# lab2_zhernakov_buck.net
KiCad netlist of a schematic drawn in Altium Designer
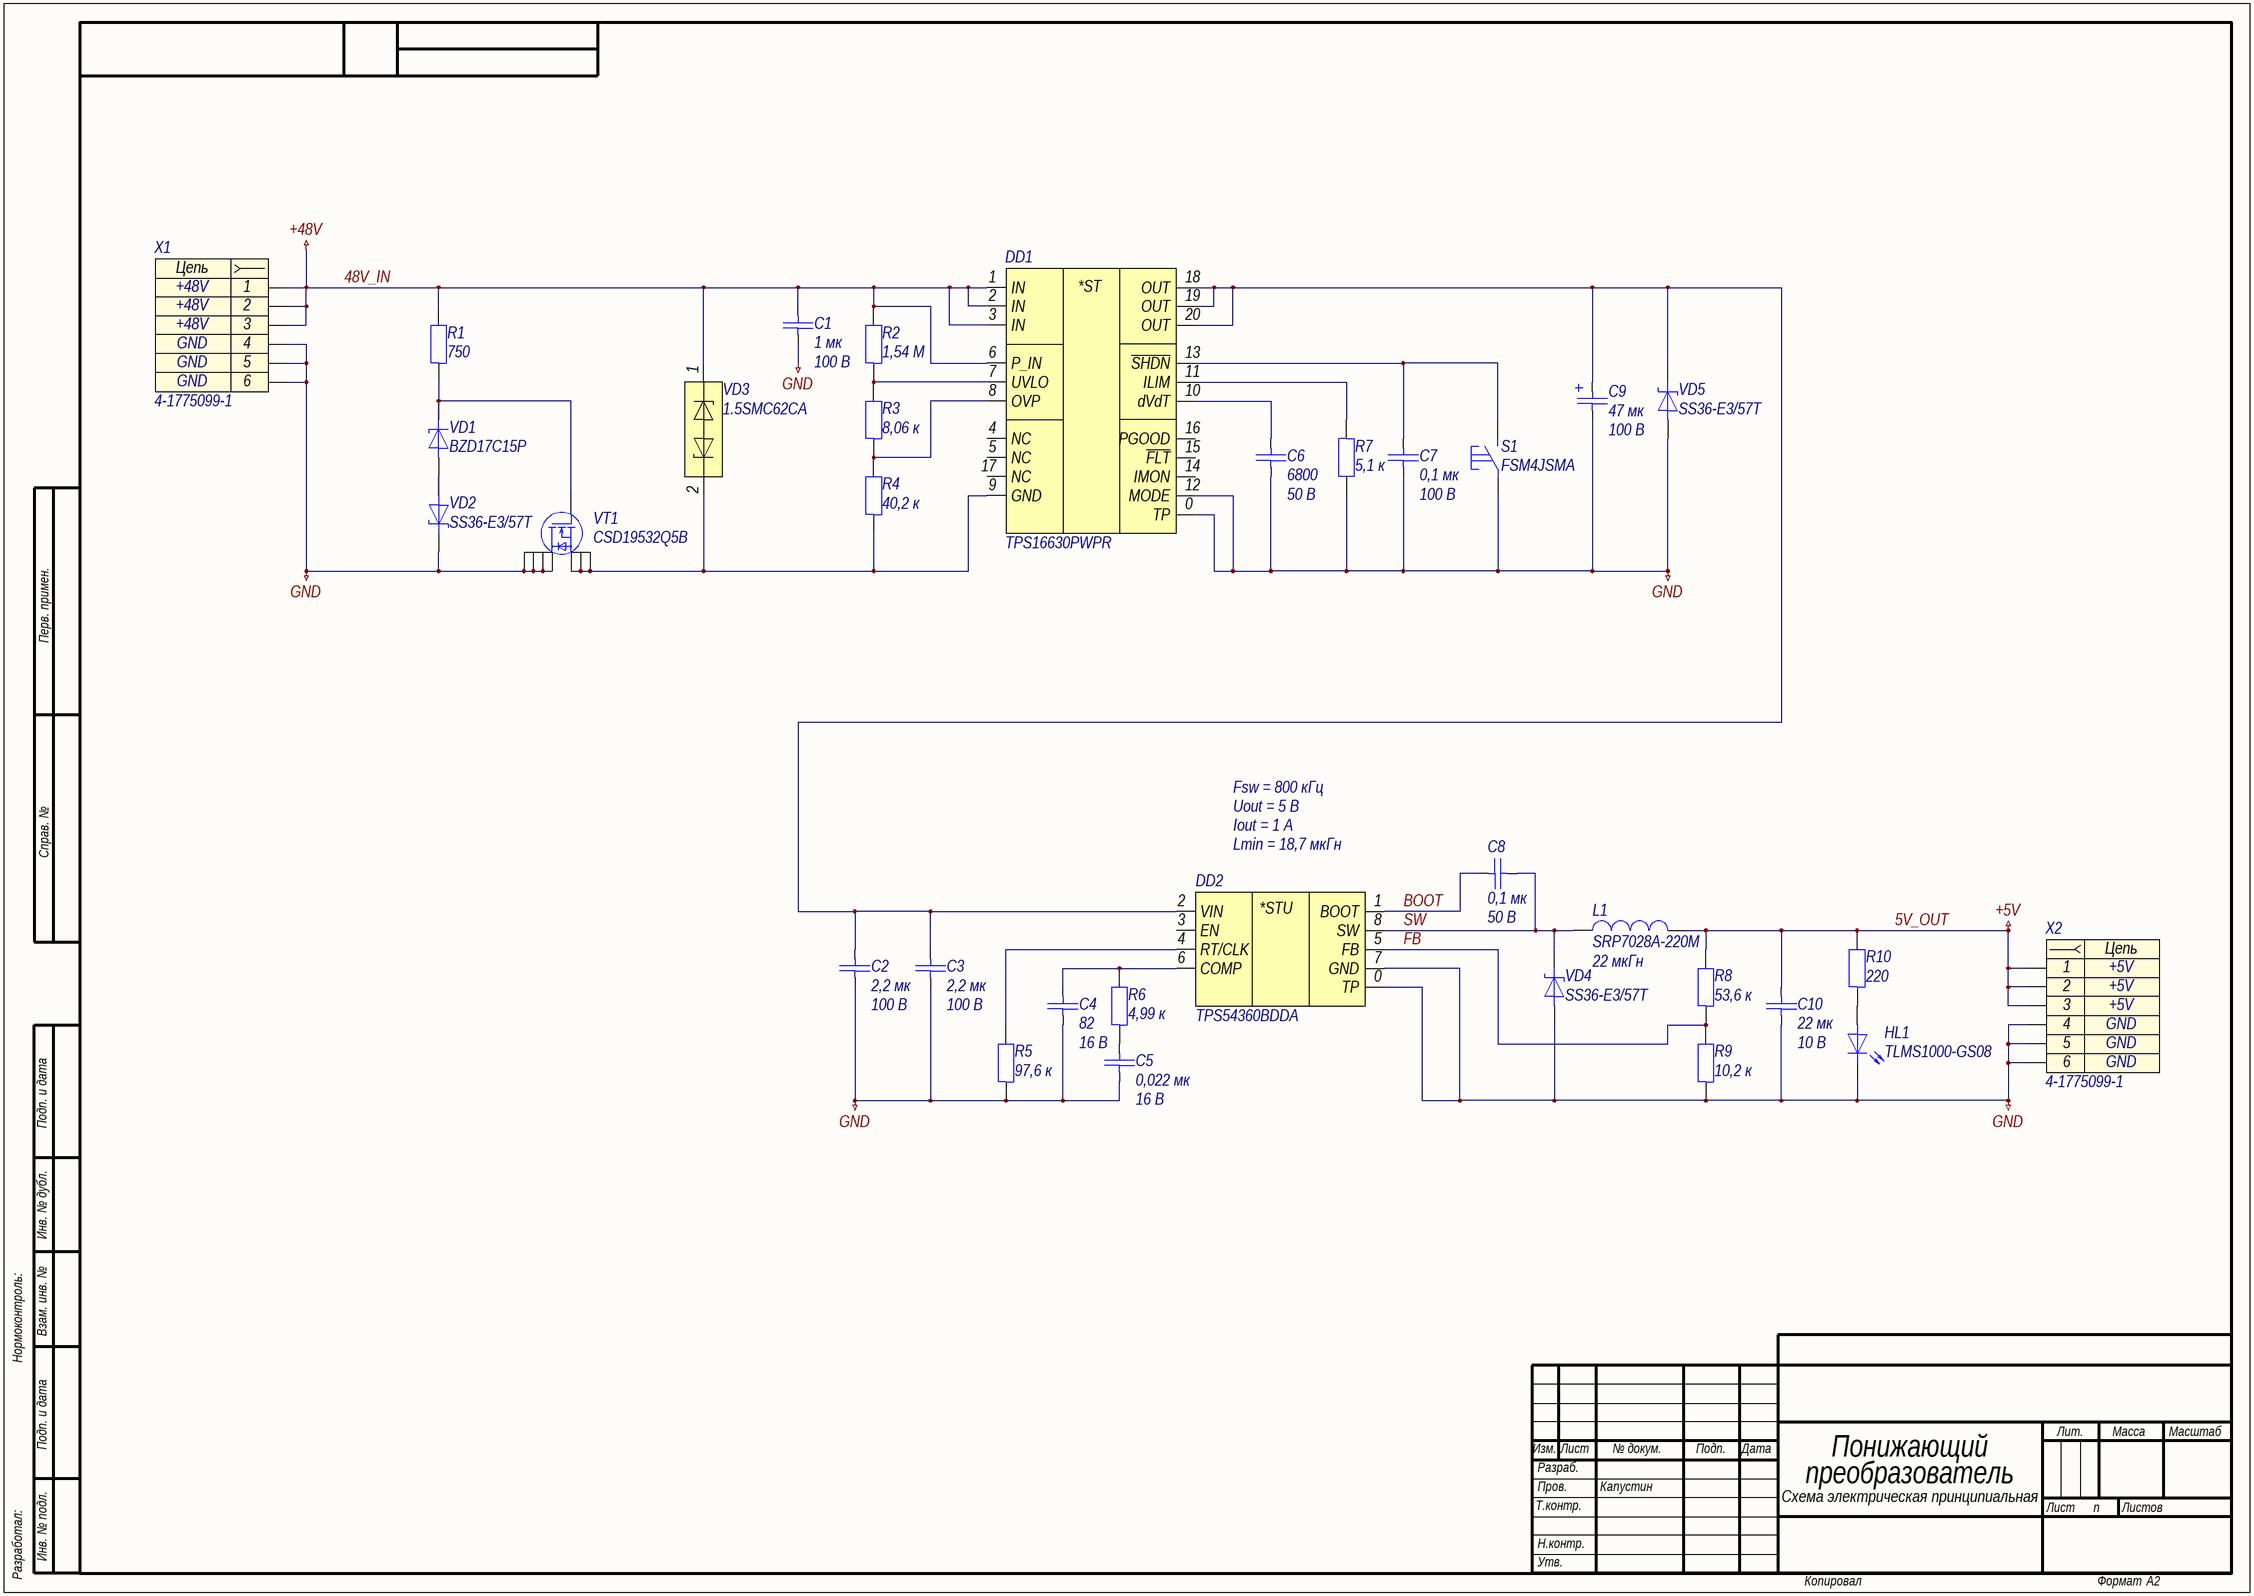
[diagram p0: lab2_zhernakov_buck.SchDoc]

(export (version "E")
  (design (tool "Eeschema 10.0.6"))
  (components
    (comp (ref "C1")
      (value "1 мк")
      (footprint "C1206")
      (description "=Описание")
      (fields (field (name "НАПРЯЖЕНИЕ") "100 В"))
      (libsource (lib "Database_Students") (part "C-NONPOLAR"))
    )
    (comp (ref "C2")
      (value "2,2 мк")
      (footprint "C1206")
      (description "=Описание")
      (fields (field (name "НАПРЯЖЕНИЕ") "100 В"))
      (libsource (lib "Database_Students") (part "C-NONPOLAR"))
    )
    (comp (ref "C3")
      (value "2,2 мк")
      (footprint "C1206")
      (description "=Описание")
      (fields (field (name "НАПРЯЖЕНИЕ") "100 В"))
      (libsource (lib "Database_Students") (part "C-NONPOLAR"))
    )
    (comp (ref "C4")
      (value "82")
      (footprint "C0603")
      (description "=Описание")
      (fields (field (name "НАПРЯЖЕНИЕ") "16 В"))
      (libsource (lib "Database_Students") (part "C-NONPOLAR"))
    )
    (comp (ref "C5")
      (value "0,022 мк")
      (footprint "C0201")
      (description "=Описание")
      (fields (field (name "НАПРЯЖЕНИЕ") "16 В"))
      (libsource (lib "Database_Students") (part "C-NONPOLAR"))
    )
    (comp (ref "C6")
      (value "6800")
      (footprint "C0402")
      (description "=Описание")
      (fields (field (name "НАПРЯЖЕНИЕ") "50 В"))
      (libsource (lib "Database_Students") (part "C-NONPOLAR"))
    )
    (comp (ref "C7")
      (value "0,1 мк")
      (footprint "C0603")
      (description "=Описание")
      (fields (field (name "НАПРЯЖЕНИЕ") "100 В"))
      (libsource (lib "Database_Students") (part "C-NONPOLAR"))
    )
    (comp (ref "C8")
      (value "0,1 мк")
      (footprint "C0603")
      (description "=Описание")
      (fields (field (name "НАПРЯЖЕНИЕ") "50 В"))
      (libsource (lib "Database_Students") (part "C-NONPOLAR"))
    )
    (comp (ref "C9")
      (value "47 мк")
      (footprint "CAPAE-1000X1000X1200")
      (description "=Описание")
      (fields (field (name "НАПРЯЖЕНИЕ") "100 В"))
      (libsource (lib "Database_Students") (part "C-POLAR"))
    )
    (comp (ref "C10")
      (value "22 мк")
      (footprint "C0603")
      (description "=Описание")
      (fields (field (name "НАПРЯЖЕНИЕ") "10 В"))
      (libsource (lib "Database_Students") (part "C-NONPOLAR"))
    )
    (comp (ref "DD1")
      (value "TPS16630PWPR")
      (footprint "HTSSOP-20")
      (description "=Описание")
      (libsource (lib "Database_Students") (part "TPS16630PWPR"))
    )
    (comp (ref "DD2")
      (value "TPS54360BDDA")
      (footprint "HSOIC-8")
      (description "=Описание")
      (libsource (lib "Database_Students") (part "TPS54360BDDA"))
    )
    (comp (ref "HL1")
      (value "TLMS1000-GS08")
      (footprint "HL0603")
      (description "=Описание")
      (libsource (lib "Database_Students") (part "HL-COMMON"))
    )
    (comp (ref "L1")
      (value "SRP7028A-220M")
      (footprint "SRP-2-670X660X280")
      (description "=Описание")
      (fields (field (name "ИНДУКТИВНОСТЬ") "22 мкГн"))
      (libsource (lib "Database_Students") (part "INDUCTOR-COMMON"))
    )
    (comp (ref "R1")
      (value "750")
      (footprint "R0603")
      (description "=Описание")
      (libsource (lib "Database_Students") (part "R-COMMON"))
    )
    (comp (ref "R2")
      (value "1,54 М")
      (footprint "R0603")
      (description "=Описание")
      (libsource (lib "Database_Students") (part "R-COMMON"))
    )
    (comp (ref "R3")
      (value "8,06 к")
      (footprint "R0603")
      (description "=Описание")
      (libsource (lib "Database_Students") (part "R-COMMON"))
    )
    (comp (ref "R4")
      (value "40,2 к")
      (footprint "R0603")
      (description "=Описание")
      (libsource (lib "Database_Students") (part "R-COMMON"))
    )
    (comp (ref "R5")
      (value "97,6 к")
      (footprint "R0603")
      (description "=Описание")
      (libsource (lib "Database_Students") (part "R-COMMON"))
    )
    (comp (ref "R6")
      (value "4,99 к")
      (footprint "R0603")
      (description "=Описание")
      (libsource (lib "Database_Students") (part "R-COMMON"))
    )
    (comp (ref "R7")
      (value "5,1 к")
      (footprint "R0603")
      (description "=Описание")
      (libsource (lib "Database_Students") (part "R-COMMON"))
    )
    (comp (ref "R8")
      (value "53,6 к")
      (footprint "R0603")
      (description "=Описание")
      (libsource (lib "Database_Students") (part "R-COMMON"))
    )
    (comp (ref "R9")
      (value "10,2 к")
      (footprint "R0603")
      (description "=Описание")
      (libsource (lib "Database_Students") (part "R-COMMON"))
    )
    (comp (ref "R10")
      (value "220")
      (footprint "R0603")
      (description "=Описание")
      (libsource (lib "Database_Students") (part "R-COMMON"))
    )
    (comp (ref "S1")
      (value "FSM4JSMA")
      (footprint "FSM4JSMA")
      (description "=Описание")
      (libsource (lib "Database_Students") (part "BUTTON"))
    )
    (comp (ref "VD1")
      (value "BZD17C15P")
      (footprint "DO-219AB")
      (description "=Описание")
      (libsource (lib "Database_Students") (part "ZENER-DIODE"))
    )
    (comp (ref "VD2")
      (value "SS36-E3/57T")
      (footprint "DO-214AB")
      (description "=Описание")
      (libsource (lib "Database_Students") (part "DIODE-SCHOTTKY"))
    )
    (comp (ref "VD3")
      (value "1.5SMC62CA")
      (footprint "DO-214AB")
      (description "=Описание")
      (libsource (lib "Database_Students") (part "ZENER-BI-DIRECTIONAL"))
    )
    (comp (ref "VD4")
      (value "SS36-E3/57T")
      (footprint "DO-214AB")
      (description "=Описание")
      (libsource (lib "Database_Students") (part "DIODE-SCHOTTKY"))
    )
    (comp (ref "VD5")
      (value "SS36-E3/57T")
      (footprint "DO-214AB")
      (description "=Описание")
      (libsource (lib "Database_Students") (part "DIODE-SCHOTTKY"))
    )
    (comp (ref "VT1")
      (value "CSD19532Q5B")
      (footprint "SON-8")
      (description "=Описание")
      (libsource (lib "Database_Students") (part "TRANSISTOR_7_N"))
    )
    (comp (ref "X1")
      (value "4-1775099-1")
      (footprint "4-1775099-1")
      (description "=Описание")
      (libsource (lib "Database_Students") (part "HEADER-6-SCT"))
    )
    (comp (ref "X2")
      (value "4-1775099-1")
      (footprint "4-1775099-1")
      (description "=Описание")
      (libsource (lib "") (part "HEADER-6-SCT_1"))
    )
  )
  (nets
    (net (code "1") (name "+5V") (class "Default")
      (node (ref "C10") (pin "1") (pinfunction "1_1") (pintype "passive"))
      (node (ref "L1") (pin "2") (pinfunction "2_2") (pintype "passive"))
      (node (ref "R10") (pin "2") (pinfunction "2_2") (pintype "passive"))
      (node (ref "R8") (pin "2") (pinfunction "2_2") (pintype "passive"))
      (node (ref "X2") (pin "1") (pinfunction "1_1") (pintype "passive"))
      (node (ref "X2") (pin "2") (pinfunction "2_2") (pintype "passive"))
      (node (ref "X2") (pin "3") (pinfunction "3_3") (pintype "passive"))
    )
    (net (code "2") (name "+48V") (class "Default")
      (node (ref "C1") (pin "1") (pinfunction "1_1") (pintype "passive"))
      (node (ref "DD1") (pin "1") (pinfunction "IN_1") (pintype "passive"))
      (node (ref "DD1") (pin "2") (pinfunction "IN_2") (pintype "passive"))
      (node (ref "DD1") (pin "3") (pinfunction "IN_3") (pintype "passive"))
      (node (ref "DD1") (pin "6") (pinfunction "P_IN_6") (pintype "passive"))
      (node (ref "R1") (pin "2") (pinfunction "2_2") (pintype "passive"))
      (node (ref "R2") (pin "2") (pinfunction "2_2") (pintype "passive"))
      (node (ref "VD3") (pin "1") (pinfunction "1_1") (pintype "passive"))
      (node (ref "X1") (pin "1") (pinfunction "1_1") (pintype "passive"))
      (node (ref "X1") (pin "2") (pinfunction "2_2") (pintype "passive"))
      (node (ref "X1") (pin "3") (pinfunction "3_3") (pintype "passive"))
    )
    (net (code "3") (name "/BOOT") (class "Default")
      (node (ref "C8") (pin "2") (pinfunction "2_2") (pintype "passive"))
      (node (ref "DD2") (pin "1") (pinfunction "BOOT_1") (pintype "passive"))
    )
    (net (code "4") (name "/FB") (class "Default")
      (node (ref "DD2") (pin "5") (pinfunction "FB_5") (pintype "passive"))
      (node (ref "R8") (pin "1") (pinfunction "1_1") (pintype "passive"))
      (node (ref "R9") (pin "2") (pinfunction "2_2") (pintype "passive"))
    )
    (net (code "5") (name "/SW") (class "Default")
      (node (ref "C8") (pin "1") (pinfunction "1_1") (pintype "passive"))
      (node (ref "DD2") (pin "8") (pinfunction "SW_8") (pintype "passive"))
      (node (ref "L1") (pin "1") (pinfunction "1_1") (pintype "passive"))
      (node (ref "VD4") (pin "1") (pinfunction "1_1") (pintype "passive"))
    )
    (net (code "6") (name "GND") (class "Default")
      (node (ref "C1") (pin "2") (pinfunction "2_2") (pintype "passive"))
      (node (ref "C10") (pin "2") (pinfunction "2_2") (pintype "passive"))
      (node (ref "C2") (pin "2") (pinfunction "2_2") (pintype "passive"))
      (node (ref "C3") (pin "2") (pinfunction "2_2") (pintype "passive"))
      (node (ref "C4") (pin "2") (pinfunction "2_2") (pintype "passive"))
      (node (ref "C5") (pin "2") (pinfunction "2_2") (pintype "passive"))
      (node (ref "C6") (pin "2") (pinfunction "2_2") (pintype "passive"))
      (node (ref "C7") (pin "2") (pinfunction "2_2") (pintype "passive"))
      (node (ref "C9") (pin "2") (pinfunction "2_2") (pintype "passive"))
      (node (ref "DD1") (pin "0") (pinfunction "TP_0") (pintype "passive"))
      (node (ref "DD1") (pin "12") (pinfunction "MODE_12") (pintype "passive"))
      (node (ref "DD2") (pin "0") (pinfunction "TP_0") (pintype "passive"))
      (node (ref "DD2") (pin "7") (pinfunction "GND_7") (pintype "passive"))
      (node (ref "HL1") (pin "1") (pinfunction "1_1") (pintype "passive"))
      (node (ref "R5") (pin "1") (pinfunction "1_1") (pintype "passive"))
      (node (ref "R7") (pin "2") (pinfunction "2_2") (pintype "passive"))
      (node (ref "R9") (pin "1") (pinfunction "1_1") (pintype "passive"))
      (node (ref "S1") (pin "1") (pinfunction "1_1") (pintype "passive"))
      (node (ref "VD2") (pin "1") (pinfunction "1_1") (pintype "passive"))
      (node (ref "VD4") (pin "2") (pinfunction "2_2") (pintype "passive"))
      (node (ref "VD5") (pin "2") (pinfunction "2_2") (pintype "passive"))
      (node (ref "VT1") (pin "D") (pinfunction "D_D") (pintype "passive"))
      (node (ref "X1") (pin "4") (pinfunction "4_4") (pintype "passive"))
      (node (ref "X1") (pin "5") (pinfunction "5_5") (pintype "passive"))
      (node (ref "X1") (pin "6") (pinfunction "6_6") (pintype "passive"))
      (node (ref "X2") (pin "4") (pinfunction "4_4") (pintype "passive"))
      (node (ref "X2") (pin "5") (pinfunction "5_5") (pintype "passive"))
      (node (ref "X2") (pin "6") (pinfunction "6_6") (pintype "passive"))
    )
    (net (code "7") (name "Net-(C5-Pad1)") (class "Default")
      (node (ref "C5") (pin "1") (pinfunction "1_1") (pintype "passive"))
      (node (ref "R6") (pin "1") (pinfunction "1_1") (pintype "passive"))
    )
    (net (code "8") (name "Net-(DD1-GND)") (class "Default")
      (node (ref "DD1") (pin "9") (pinfunction "GND_9") (pintype "passive"))
      (node (ref "R4") (pin "1") (pinfunction "1_1") (pintype "passive"))
      (node (ref "VD3") (pin "2") (pinfunction "2_2") (pintype "passive"))
      (node (ref "VT1") (pin "S") (pinfunction "S_S") (pintype "passive"))
    )
    (net (code "9") (name "Net-(DD1-ILIM)") (class "Default")
      (node (ref "DD1") (pin "11") (pinfunction "ILIM_11") (pintype "passive"))
      (node (ref "R7") (pin "1") (pinfunction "1_1") (pintype "passive"))
    )
    (net (code "10") (name "Net-(DD1-OVP)") (class "Default")
      (node (ref "DD1") (pin "8") (pinfunction "OVP_8") (pintype "passive"))
      (node (ref "R3") (pin "1") (pinfunction "1_1") (pintype "passive"))
      (node (ref "R4") (pin "2") (pinfunction "2_2") (pintype "passive"))
    )
    (net (code "11") (name "Net-(DD1-UVLO)") (class "Default")
      (node (ref "DD1") (pin "7") (pinfunction "UVLO_7") (pintype "passive"))
      (node (ref "R2") (pin "1") (pinfunction "1_1") (pintype "passive"))
      (node (ref "R3") (pin "2") (pinfunction "2_2") (pintype "passive"))
    )
    (net (code "12") (name "Net-(DD1-dVdT)") (class "Default")
      (node (ref "C6") (pin "1") (pinfunction "1_1") (pintype "passive"))
      (node (ref "DD1") (pin "10") (pinfunction "dVdT_10") (pintype "passive"))
    )
    (net (code "13") (name "Net-(DD1-~{SHDN})") (class "Default")
      (node (ref "C7") (pin "1") (pinfunction "1_1") (pintype "passive"))
      (node (ref "DD1") (pin "13") (pinfunction "~{SHDN}_13") (pintype "passive"))
      (node (ref "S1") (pin "2") (pinfunction "2_2") (pintype "passive"))
    )
    (net (code "14") (name "Net-(DD2-COMP)") (class "Default")
      (node (ref "C4") (pin "1") (pinfunction "1_1") (pintype "passive"))
      (node (ref "DD2") (pin "6") (pinfunction "COMP_6") (pintype "passive"))
      (node (ref "R6") (pin "2") (pinfunction "2_2") (pintype "passive"))
    )
    (net (code "15") (name "Net-(DD2-RT{slash}CLK)") (class "Default")
      (node (ref "DD2") (pin "4") (pinfunction "RT/CLK_4") (pintype "passive"))
      (node (ref "R5") (pin "2") (pinfunction "2_2") (pintype "passive"))
    )
    (net (code "16") (name "Net-(DD2-VIN)") (class "Default")
      (node (ref "C2") (pin "1") (pinfunction "1_1") (pintype "passive"))
      (node (ref "C3") (pin "1") (pinfunction "1_1") (pintype "passive"))
      (node (ref "C9") (pin "1") (pinfunction "1_1") (pintype "passive"))
      (node (ref "DD1") (pin "18") (pinfunction "OUT_18") (pintype "passive"))
      (node (ref "DD1") (pin "19") (pinfunction "OUT_19") (pintype "passive"))
      (node (ref "DD1") (pin "20") (pinfunction "OUT_20") (pintype "passive"))
      (node (ref "DD2") (pin "2") (pinfunction "VIN_2") (pintype "passive"))
      (node (ref "VD5") (pin "1") (pinfunction "1_1") (pintype "passive"))
    )
    (net (code "17") (name "Net-(HL1-Pad2)") (class "Default")
      (node (ref "HL1") (pin "2") (pinfunction "2_2") (pintype "passive"))
      (node (ref "R10") (pin "1") (pinfunction "1_1") (pintype "passive"))
    )
    (net (code "18") (name "Net-(R1-Pad1)") (class "Default")
      (node (ref "R1") (pin "1") (pinfunction "1_1") (pintype "passive"))
      (node (ref "VD1") (pin "1") (pinfunction "1_1") (pintype "passive"))
      (node (ref "VT1") (pin "G") (pinfunction "G_G") (pintype "passive"))
    )
    (net (code "19") (name "Net-(VD1-Pad2)") (class "Default")
      (node (ref "VD1") (pin "2") (pinfunction "2_2") (pintype "passive"))
      (node (ref "VD2") (pin "2") (pinfunction "2_2") (pintype "passive"))
    )
    (net (code "20") (name "unconnected-(DD1-IMON-Pad14)") (class "Default")
      (node (ref "DD1") (pin "14") (pinfunction "IMON_14") (pintype "passive"))
    )
    (net (code "21") (name "unconnected-(DD1-NC-Pad4)") (class "Default")
      (node (ref "DD1") (pin "4") (pinfunction "NC_4") (pintype "passive"))
    )
    (net (code "22") (name "unconnected-(DD1-NC-Pad5)") (class "Default")
      (node (ref "DD1") (pin "5") (pinfunction "NC_5") (pintype "passive"))
    )
    (net (code "23") (name "unconnected-(DD1-NC-Pad17)") (class "Default")
      (node (ref "DD1") (pin "17") (pinfunction "NC_17") (pintype "passive"))
    )
    (net (code "24") (name "unconnected-(DD1-PGOOD-Pad16)") (class "Default")
      (node (ref "DD1") (pin "16") (pinfunction "PGOOD_16") (pintype "passive"))
    )
    (net (code "25") (name "unconnected-(DD1-~{FLT}-Pad15)") (class "Default")
      (node (ref "DD1") (pin "15") (pinfunction "~{FLT}_15") (pintype "passive"))
    )
    (net (code "26") (name "unconnected-(DD2-EN-Pad3)") (class "Default")
      (node (ref "DD2") (pin "3") (pinfunction "EN_3") (pintype "passive"))
    )
  )
)
